# Buck_Converter.net
KiCad netlist of a schematic drawn in Altium Designer
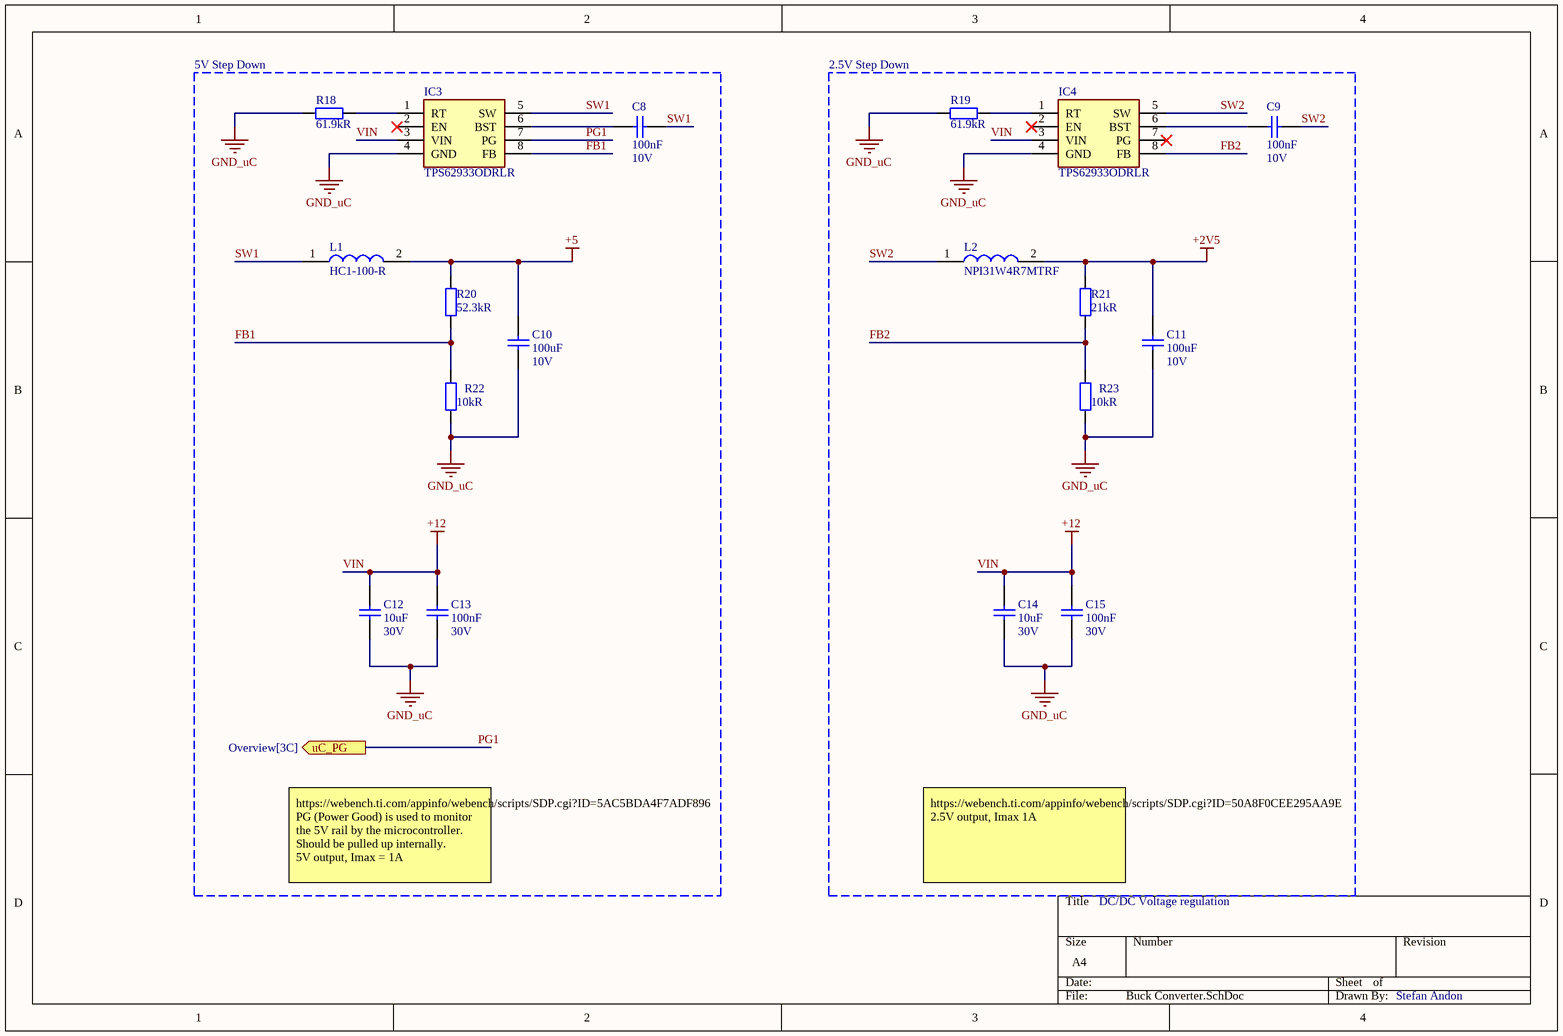
[diagram p0: Buck Converter.SchDoc]

(export (version "E")
  (design (tool "Eeschema 10.0.6"))
  (components
    (comp (ref "C8")
      (value "100nF")
      (footprint "CAP_0603")
      (description "SMD Capacitor")
      (fields
        (field (name "TOLERANCE") "tbd")
        (field (name "VOLTAGE") "10V")
        (field (name "Comment") "Capacitor_SMD")
      )
      (libsource (lib "TUfast e") (part "SMD Capacitor"))
    )
    (comp (ref "C9")
      (value "100nF")
      (footprint "CAP_0603")
      (description "SMD Capacitor")
      (fields
        (field (name "TOLERANCE") "tbd")
        (field (name "VOLTAGE") "10V")
        (field (name "Comment") "Capacitor_SMD")
      )
      (libsource (lib "TUfast e") (part "SMD Capacitor"))
    )
    (comp (ref "C10")
      (value "100uF")
      (footprint "CAP_0603")
      (description "SMD Capacitor")
      (fields
        (field (name "TOLERANCE") "tbd")
        (field (name "VOLTAGE") "10V")
        (field (name "Comment") "Capacitor_SMD")
      )
      (libsource (lib "TUfast e") (part "SMD Capacitor"))
    )
    (comp (ref "C11")
      (value "100uF")
      (footprint "CAP_0603")
      (description "SMD Capacitor")
      (fields
        (field (name "TOLERANCE") "tbd")
        (field (name "VOLTAGE") "10V")
        (field (name "Comment") "Capacitor_SMD")
      )
      (libsource (lib "TUfast e") (part "SMD Capacitor"))
    )
    (comp (ref "C12")
      (value "10uF")
      (footprint "CAP_0603")
      (description "SMD Capacitor")
      (fields
        (field (name "TOLERANCE") "tbd")
        (field (name "VOLTAGE") "30V")
        (field (name "Comment") "Capacitor_SMD")
      )
      (libsource (lib "TUfast e") (part "SMD Capacitor"))
    )
    (comp (ref "C13")
      (value "100nF")
      (footprint "CAP_0603")
      (description "SMD Capacitor")
      (fields
        (field (name "TOLERANCE") "tbd")
        (field (name "VOLTAGE") "30V")
        (field (name "Comment") "Capacitor_SMD")
      )
      (libsource (lib "TUfast e") (part "SMD Capacitor"))
    )
    (comp (ref "C14")
      (value "10uF")
      (footprint "CAP_0603")
      (description "SMD Capacitor")
      (fields
        (field (name "TOLERANCE") "tbd")
        (field (name "VOLTAGE") "30V")
        (field (name "Comment") "Capacitor_SMD")
      )
      (libsource (lib "TUfast e") (part "SMD Capacitor"))
    )
    (comp (ref "C15")
      (value "100nF")
      (footprint "CAP_0603")
      (description "SMD Capacitor")
      (fields
        (field (name "TOLERANCE") "tbd")
        (field (name "VOLTAGE") "30V")
        (field (name "Comment") "Capacitor_SMD")
      )
      (libsource (lib "TUfast e") (part "SMD Capacitor"))
    )
    (comp (ref "IC3")
      (value "TPS62933ODRLR")
      (footprint "SamacSys:SOTFL50P160X60-8N")
      (description "Integrated Circuit")
      (fields (field (name "MOUSER PART NUMBER") "595-TPS62933ODRLR"))
      (libsource (lib "*") (part "TPS62933ODRLR"))
    )
    (comp (ref "IC4")
      (value "TPS62933ODRLR")
      (footprint "SamacSys:SOTFL50P160X60-8N")
      (description "Integrated Circuit")
      (fields (field (name "MOUSER PART NUMBER") "595-TPS62933ODRLR"))
      (libsource (lib "*") (part "TPS62933ODRLR"))
    )
    (comp (ref "L1")
      (value "HC1-100-R")
      (footprint "SamacSys:HC1100R")
      (description "Inductor")
      (fields (field (name "MOUSER PART NUMBER") "704-HC1-100-R"))
      (libsource (lib "*") (part "HC1-100-R"))
    )
    (comp (ref "L2")
      (value "NPI31W4R7MTRF")
      (footprint "SamacSys:NPI31W4R7MTRF")
      (description "Inductor")
      (libsource (lib "*") (part "NPI31W4R7MTRF"))
    )
    (comp (ref "R18")
      (value "61.9kR")
      (footprint "RES_1206")
      (fields
        (field (name "TOLERANCE") "tbd")
        (field (name "POWER") "7W")
        (field (name "Comment") "Resistor_SMD")
      )
      (libsource (lib "") (part "Resistor_1"))
    )
    (comp (ref "R19")
      (value "61.9kR")
      (footprint "RES_1206")
      (fields
        (field (name "TOLERANCE") "tbd")
        (field (name "POWER") "7W")
        (field (name "Comment") "Resistor_SMD")
      )
      (libsource (lib "") (part "Resistor_1"))
    )
    (comp (ref "R20")
      (value "52.3kR")
      (footprint "RES_1206")
      (fields
        (field (name "TOLERANCE") "tbd")
        (field (name "POWER") "7W")
        (field (name "Comment") "Resistor_SMD")
      )
      (libsource (lib "TUfast e") (part "Resistor"))
    )
    (comp (ref "R21")
      (value "21kR")
      (footprint "RES_1206")
      (fields
        (field (name "TOLERANCE") "tbd")
        (field (name "POWER") "7W")
        (field (name "Comment") "Resistor_SMD")
      )
      (libsource (lib "TUfast e") (part "Resistor"))
    )
    (comp (ref "R22")
      (value "10kR")
      (footprint "RES_1206")
      (fields
        (field (name "TOLERANCE") "tbd")
        (field (name "POWER") "7W")
        (field (name "Comment") "Resistor_SMD")
      )
      (libsource (lib "TUfast e") (part "Resistor"))
    )
    (comp (ref "R23")
      (value "10kR")
      (footprint "RES_1206")
      (fields
        (field (name "TOLERANCE") "tbd")
        (field (name "POWER") "7W")
        (field (name "Comment") "Resistor_SMD")
      )
      (libsource (lib "TUfast e") (part "Resistor"))
    )
  )
  (nets
    (net (code "1") (name "+2V5") (class "Default")
      (node (ref "C11") (pin "2") (pinfunction "2_2") (pintype "passive"))
      (node (ref "L2") (pin "2") (pinfunction "2_2") (pintype "passive"))
      (node (ref "R21") (pin "1") (pinfunction "1_1") (pintype "passive"))
    )
    (net (code "2") (name "+5") (class "Default")
      (node (ref "C10") (pin "2") (pinfunction "2_2") (pintype "passive"))
      (node (ref "L1") (pin "2") (pinfunction "2_2") (pintype "passive"))
      (node (ref "R20") (pin "1") (pinfunction "1_1") (pintype "passive"))
    )
    (net (code "3") (name "+12") (class "Default")
      (node (ref "C12") (pin "2") (pinfunction "2_2") (pintype "passive"))
      (node (ref "C13") (pin "2") (pinfunction "2_2") (pintype "passive"))
      (node (ref "C14") (pin "2") (pinfunction "2_2") (pintype "passive"))
      (node (ref "C15") (pin "2") (pinfunction "2_2") (pintype "passive"))
      (node (ref "IC3") (pin "3") (pinfunction "VIN_3") (pintype "passive"))
      (node (ref "IC4") (pin "3") (pinfunction "VIN_3") (pintype "passive"))
    )
    (net (code "4") (name "/FB1") (class "Default")
      (node (ref "IC3") (pin "8") (pinfunction "FB_8") (pintype "passive"))
      (node (ref "R20") (pin "2") (pinfunction "2_2") (pintype "passive"))
      (node (ref "R22") (pin "1") (pinfunction "1_1") (pintype "passive"))
    )
    (net (code "5") (name "/FB2") (class "Default")
      (node (ref "IC4") (pin "8") (pinfunction "FB_8") (pintype "passive"))
      (node (ref "R21") (pin "2") (pinfunction "2_2") (pintype "passive"))
      (node (ref "R23") (pin "1") (pinfunction "1_1") (pintype "passive"))
    )
    (net (code "6") (name "/PG1") (class "Default")
      (node (ref "IC3") (pin "7") (pinfunction "PG_7") (pintype "passive"))
    )
    (net (code "7") (name "/SW1") (class "Default")
      (node (ref "C8") (pin "1") (pinfunction "1_1") (pintype "passive"))
      (node (ref "IC3") (pin "5") (pinfunction "SW_5") (pintype "passive"))
      (node (ref "L1") (pin "1") (pinfunction "1_1") (pintype "passive"))
    )
    (net (code "8") (name "/SW2") (class "Default")
      (node (ref "C9") (pin "1") (pinfunction "1_1") (pintype "passive"))
      (node (ref "IC4") (pin "5") (pinfunction "SW_5") (pintype "passive"))
      (node (ref "L2") (pin "1") (pinfunction "1_1") (pintype "passive"))
    )
    (net (code "9") (name "GND_uC") (class "Default")
      (node (ref "C10") (pin "1") (pinfunction "1_1") (pintype "passive"))
      (node (ref "C11") (pin "1") (pinfunction "1_1") (pintype "passive"))
      (node (ref "C12") (pin "1") (pinfunction "1_1") (pintype "passive"))
      (node (ref "C13") (pin "1") (pinfunction "1_1") (pintype "passive"))
      (node (ref "C14") (pin "1") (pinfunction "1_1") (pintype "passive"))
      (node (ref "C15") (pin "1") (pinfunction "1_1") (pintype "passive"))
      (node (ref "IC3") (pin "4") (pinfunction "GND_4") (pintype "passive"))
      (node (ref "IC4") (pin "4") (pinfunction "GND_4") (pintype "passive"))
      (node (ref "R18") (pin "1") (pinfunction "1_1") (pintype "passive"))
      (node (ref "R19") (pin "1") (pinfunction "1_1") (pintype "passive"))
      (node (ref "R22") (pin "2") (pinfunction "2_2") (pintype "passive"))
      (node (ref "R23") (pin "2") (pinfunction "2_2") (pintype "passive"))
    )
    (net (code "10") (name "Net-(IC3-BST)") (class "Default")
      (node (ref "C8") (pin "2") (pinfunction "2_2") (pintype "passive"))
      (node (ref "IC3") (pin "6") (pinfunction "BST_6") (pintype "passive"))
    )
    (net (code "11") (name "Net-(IC3-RT)") (class "Default")
      (node (ref "IC3") (pin "1") (pinfunction "RT_1") (pintype "passive"))
      (node (ref "R18") (pin "2") (pinfunction "2_2") (pintype "passive"))
    )
    (net (code "12") (name "Net-(IC4-BST)") (class "Default")
      (node (ref "C9") (pin "2") (pinfunction "2_2") (pintype "passive"))
      (node (ref "IC4") (pin "6") (pinfunction "BST_6") (pintype "passive"))
    )
    (net (code "13") (name "Net-(IC4-RT)") (class "Default")
      (node (ref "IC4") (pin "1") (pinfunction "RT_1") (pintype "passive"))
      (node (ref "R19") (pin "2") (pinfunction "2_2") (pintype "passive"))
    )
    (net (code "14") (name "unconnected-(IC3-EN-Pad2)") (class "Default")
      (node (ref "IC3") (pin "2") (pinfunction "EN_2") (pintype "passive+no_connect"))
    )
    (net (code "15") (name "unconnected-(IC4-EN-Pad2)") (class "Default")
      (node (ref "IC4") (pin "2") (pinfunction "EN_2") (pintype "passive+no_connect"))
    )
    (net (code "16") (name "unconnected-(IC4-PG-Pad7)") (class "Default")
      (node (ref "IC4") (pin "7") (pinfunction "PG_7") (pintype "passive+no_connect"))
    )
  )
)
